# schematic.net
KiCad netlist of a schematic drawn in EasyEDA
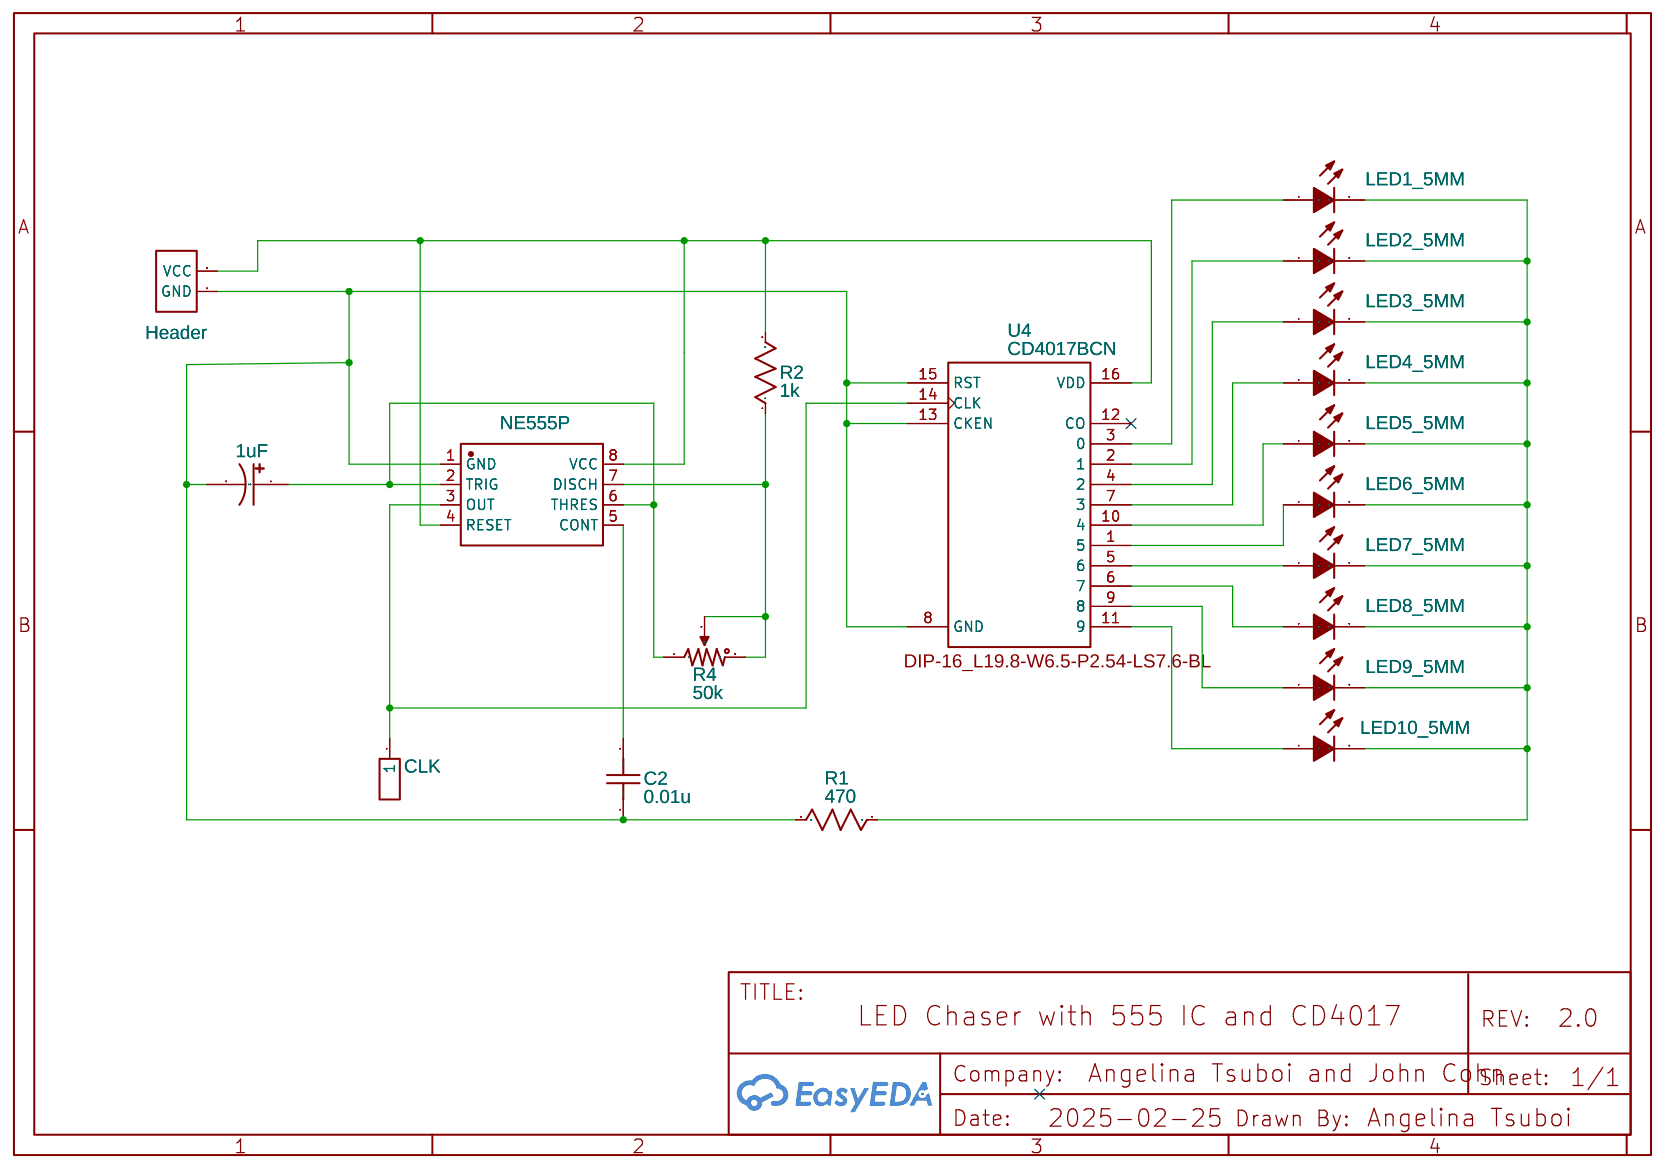
[diagram p0: schematic sheet]

(export (version "E")
  (design (tool "Eeschema 10.0.6"))
  (components
    (comp (ref "C1")
      (value "1uF")
      (fields (field (name "Manufacturer Part") "UVZ1H010MDD") (field (name "Manufacturer") "Nichicon(尼吉康)"))
      (libsource (lib "") (part "UVZ1H010MDD"))
    )
    (comp (ref "C2") (value "0.01u") (libsource (lib "") (part "C_0603_US")))
    (comp (ref "CLK")
      (value "C81276")
      (fields
        (field (name "Manufacturer Part") "2.54-1*1P针")
        (field (name "Manufacturer") "BOOMELE(Boom Precision Elec)")
      )
      (libsource (lib "") (part "Header-Male-2.54_1x1"))
    )
    (comp (ref "H1") (value "Header") (libsource (lib "") (part "HEADER-FEMALE-2.54_1X2")))
    (comp (ref "LED1_5MM") (value "LED_5MM") (libsource (lib "") (part "LED_5MM")))
    (comp (ref "LED2_5MM") (value "LED_5MM") (libsource (lib "") (part "LED_5MM_4")))
    (comp (ref "LED3_5MM") (value "LED_5MM") (libsource (lib "") (part "LED_5MM_8")))
    (comp (ref "LED4_5MM") (value "LED_5MM") (libsource (lib "") (part "LED_5MM_3")))
    (comp (ref "LED5_5MM") (value "LED_5MM") (libsource (lib "") (part "LED_5MM_5")))
    (comp (ref "LED6_5MM") (value "LED_5MM") (libsource (lib "") (part "LED_5MM_2")))
    (comp (ref "LED7_5MM") (value "LED_5MM") (libsource (lib "") (part "LED_5MM_7")))
    (comp (ref "LED8_5MM") (value "LED_5MM") (libsource (lib "") (part "LED_5MM_6")))
    (comp (ref "LED9_5MM") (value "LED_5MM") (libsource (lib "") (part "LED_5MM_9")))
    (comp (ref "LED10_5MM") (value "LED_5MM") (libsource (lib "") (part "LED_5MM_1")))
    (comp (ref "R1")
      (value "470")
      (fields (field (name "Manufacturer Part") "?"))
      (libsource (lib "") (part "Resistor_1"))
    )
    (comp (ref "R2")
      (value "1k")
      (fields (field (name "Manufacturer Part") "?"))
      (libsource (lib "") (part "Resistor"))
    )
    (comp (ref "R4")
      (value "50k")
      (fields (field (name "Manufacturer Part") "?"))
      (libsource (lib "") (part "Potentiometer"))
    )
    (comp (ref "U2")
      (value "NE555P")
      (fields (field (name "Manufacturer") "TI(德州仪器)"))
      (libsource (lib "") (part "NE555P"))
    )
    (comp (ref "U4") (value "CD4017BCN") (libsource (lib "") (part "CD4017BCN")))
  )
  (nets
    (net (code "1") (name "Net-(H1-GND)") (class "Default")
      (node (ref "C1") (pin "2") (pinfunction "2_2") (pintype "unspecified"))
      (node (ref "C2") (pin "2") (pinfunction "2_2") (pintype "unspecified"))
      (node (ref "H1") (pin "2") (pinfunction "GND_2") (pintype "unspecified"))
      (node (ref "R1") (pin "2") (pinfunction "2_2") (pintype "unspecified"))
      (node (ref "U2") (pin "1") (pinfunction "GND_1") (pintype "unspecified"))
      (node (ref "U4") (pin "13") (pinfunction "CKEN_13") (pintype "unspecified"))
      (node (ref "U4") (pin "15") (pinfunction "RST_15") (pintype "unspecified"))
      (node (ref "U4") (pin "8") (pinfunction "GND_8") (pintype "passive"))
    )
    (net (code "2") (name "Net-(H1-VCC)") (class "Default")
      (node (ref "H1") (pin "1") (pinfunction "VCC_1") (pintype "unspecified"))
      (node (ref "R2") (pin "2") (pinfunction "2_2") (pintype "unspecified"))
      (node (ref "U2") (pin "4") (pinfunction "RESET_4") (pintype "unspecified"))
      (node (ref "U2") (pin "8") (pinfunction "VCC_8") (pintype "unspecified"))
      (node (ref "U4") (pin "16") (pinfunction "VDD_16") (pintype "passive"))
    )
    (net (code "3") (name "Net-(LED1_5MM-A)") (class "Default")
      (node (ref "LED1_5MM") (pin "1") (pinfunction "A_1") (pintype "input"))
      (node (ref "U4") (pin "3") (pinfunction "0_3") (pintype "output"))
    )
    (net (code "4") (name "Net-(LED2_5MM-A)") (class "Default")
      (node (ref "LED2_5MM") (pin "1") (pinfunction "A_1") (pintype "input"))
      (node (ref "U4") (pin "2") (pinfunction "1_2") (pintype "output"))
    )
    (net (code "5") (name "Net-(LED3_5MM-A)") (class "Default")
      (node (ref "LED3_5MM") (pin "1") (pinfunction "A_1") (pintype "input"))
      (node (ref "U4") (pin "4") (pinfunction "2_4") (pintype "output"))
    )
    (net (code "6") (name "Net-(LED4_5MM-A)") (class "Default")
      (node (ref "LED4_5MM") (pin "1") (pinfunction "A_1") (pintype "input"))
      (node (ref "U4") (pin "7") (pinfunction "3_7") (pintype "output"))
    )
    (net (code "7") (name "Net-(LED5_5MM-A)") (class "Default")
      (node (ref "LED5_5MM") (pin "1") (pinfunction "A_1") (pintype "input"))
      (node (ref "U4") (pin "10") (pinfunction "4_10") (pintype "output"))
    )
    (net (code "8") (name "Net-(LED6_5MM-A)") (class "Default")
      (node (ref "LED6_5MM") (pin "1") (pinfunction "A_1") (pintype "input"))
      (node (ref "U4") (pin "1") (pinfunction "5_1") (pintype "output"))
    )
    (net (code "9") (name "Net-(LED7_5MM-A)") (class "Default")
      (node (ref "LED7_5MM") (pin "1") (pinfunction "A_1") (pintype "input"))
      (node (ref "U4") (pin "5") (pinfunction "6_5") (pintype "output"))
    )
    (net (code "10") (name "Net-(LED8_5MM-A)") (class "Default")
      (node (ref "LED8_5MM") (pin "1") (pinfunction "A_1") (pintype "input"))
      (node (ref "U4") (pin "6") (pinfunction "7_6") (pintype "output"))
    )
    (net (code "11") (name "Net-(LED9_5MM-A)") (class "Default")
      (node (ref "LED9_5MM") (pin "1") (pinfunction "A_1") (pintype "input"))
      (node (ref "U4") (pin "9") (pinfunction "8_9") (pintype "output"))
    )
    (net (code "12") (name "Net-(LED10_5MM-A)") (class "Default")
      (node (ref "LED10_5MM") (pin "1") (pinfunction "A_1") (pintype "input"))
      (node (ref "U4") (pin "11") (pinfunction "9_11") (pintype "output"))
    )
    (net (code "13") (name "Net-(LED10_5MM-K)") (class "Default")
      (node (ref "LED10_5MM") (pin "2") (pinfunction "K_2") (pintype "input"))
      (node (ref "LED1_5MM") (pin "2") (pinfunction "K_2") (pintype "input"))
      (node (ref "LED2_5MM") (pin "2") (pinfunction "K_2") (pintype "input"))
      (node (ref "LED3_5MM") (pin "2") (pinfunction "K_2") (pintype "input"))
      (node (ref "LED4_5MM") (pin "2") (pinfunction "K_2") (pintype "input"))
      (node (ref "LED5_5MM") (pin "2") (pinfunction "K_2") (pintype "input"))
      (node (ref "LED6_5MM") (pin "2") (pinfunction "K_2") (pintype "input"))
      (node (ref "LED7_5MM") (pin "2") (pinfunction "K_2") (pintype "input"))
      (node (ref "LED8_5MM") (pin "2") (pinfunction "K_2") (pintype "input"))
      (node (ref "LED9_5MM") (pin "2") (pinfunction "K_2") (pintype "input"))
      (node (ref "R1") (pin "1") (pinfunction "1_1") (pintype "unspecified"))
    )
    (net (code "14") (name "Net-(R4-2)") (class "Default")
      (node (ref "R2") (pin "1") (pinfunction "1_1") (pintype "unspecified"))
      (node (ref "R4") (pin "2") (pinfunction "3_2") (pintype "unspecified"))
      (node (ref "R4") (pin "3") (pinfunction "2_3") (pintype "unspecified"))
      (node (ref "U2") (pin "7") (pinfunction "DISCH_7") (pintype "unspecified"))
    )
    (net (code "15") (name "Net-(U2-CONT)") (class "Default")
      (node (ref "C2") (pin "1") (pinfunction "1_1") (pintype "unspecified"))
      (node (ref "U2") (pin "5") (pinfunction "CONT_5") (pintype "unspecified"))
    )
    (net (code "16") (name "Net-(U2-OUT)") (class "Default")
      (node (ref "CLK") (pin "1") (pinfunction "1_1") (pintype "unspecified"))
      (node (ref "U2") (pin "3") (pinfunction "OUT_3") (pintype "unspecified"))
      (node (ref "U4") (pin "14") (pinfunction "CLK_14") (pintype "unspecified"))
    )
    (net (code "17") (name "Net-(U2-THRES)") (class "Default")
      (node (ref "C1") (pin "1") (pinfunction "1_1") (pintype "unspecified"))
      (node (ref "R4") (pin "1") (pinfunction "1_1") (pintype "unspecified"))
      (node (ref "U2") (pin "2") (pinfunction "TRIG_2") (pintype "unspecified"))
      (node (ref "U2") (pin "6") (pinfunction "THRES_6") (pintype "unspecified"))
    )
    (net (code "18") (name "unconnected-(U4-CO-Pad12)") (class "Default")
      (node (ref "U4") (pin "12") (pinfunction "CO_12") (pintype "output+no_connect"))
    )
  )
)
